# SENSOR.net
KiCad netlist of a schematic drawn in Altium Designer
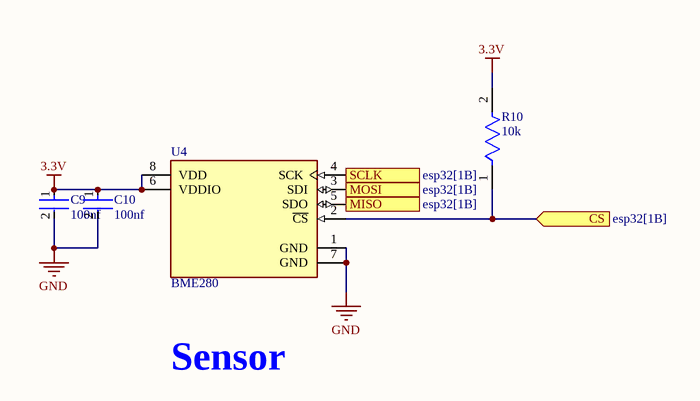
[diagram p0: SENSOR.SchDoc]

(export (version "E")
  (design (tool "Eeschema 10.0.6"))
  (components
    (comp (ref "C9")
      (value "100nf")
      (footprint "FP-CC0603-DA-MFG")
      (description "CAP CER 0.1UF 50V X7R 0603")
      (fields (field (name "MANUFACTURER") "YAGEO") (field (name "VOLTAGE") "50 V"))
      (libsource (lib "Altium Content Vault") (part "11868f565c42a9108669ba33697ecf6"))
    )
    (comp (ref "C10")
      (value "100nf")
      (footprint "FP-CC0603-DA-MFG")
      (description "CAP CER 0.1UF 50V X7R 0603")
      (fields (field (name "MANUFACTURER") "YAGEO") (field (name "VOLTAGE") "50 V"))
      (libsource (lib "Altium Content Vault") (part "11868f565c42a9108669ba33697ecf6"))
    )
    (comp (ref "R10")
      (value "10k")
      (footprint "FP-RC0603-0_55-IPC_C")
      (description "RES 10K OHM 1% 1/10W 0603")
      (fields (field (name "TOLERANCE") "1%"))
      (libsource (lib "Altium Content Vault") (part "1029c3af85768c4190bb7ad29bc67b5"))
    )
    (comp (ref "U4")
      (value "BME280")
      (footprint "FP-BME280-MFG")
      (description "SENSOR PRESSURE HUMIDITY TEMP")
      (libsource (lib "Altium Content Vault") (part "d58e2f6669bc67e6a2bc6a28610ca79"))
    )
  )
  (nets
    (net (code "1") (name "/CS") (class "Default")
      (node (ref "R10") (pin "1") (pinfunction "1_1") (pintype "passive"))
      (node (ref "U4") (pin "2") (pinfunction "~{CS}_2") (pintype "input"))
    )
    (net (code "2") (name "/MISO") (class "Default")
      (node (ref "U4") (pin "5") (pinfunction "SDO_5") (pintype "bidirectional"))
    )
    (net (code "3") (name "/MOSI") (class "Default")
      (node (ref "U4") (pin "3") (pinfunction "SDI_3") (pintype "bidirectional"))
    )
    (net (code "4") (name "/SCLK") (class "Default")
      (node (ref "U4") (pin "4") (pinfunction "SCK_4") (pintype "input"))
    )
    (net (code "5") (name "3.3V") (class "Default")
      (node (ref "C10") (pin "1") (pinfunction "1_1") (pintype "passive"))
      (node (ref "C9") (pin "1") (pinfunction "1_1") (pintype "passive"))
      (node (ref "R10") (pin "2") (pinfunction "2_2") (pintype "passive"))
      (node (ref "U4") (pin "6") (pinfunction "VDDIO_6") (pintype "power_in"))
      (node (ref "U4") (pin "8") (pinfunction "VDD_8") (pintype "power_in"))
    )
    (net (code "6") (name "GND") (class "Default")
      (node (ref "C10") (pin "2") (pinfunction "2_2") (pintype "passive"))
      (node (ref "C9") (pin "2") (pinfunction "2_2") (pintype "passive"))
      (node (ref "U4") (pin "1") (pinfunction "GND_1") (pintype "power_in"))
      (node (ref "U4") (pin "7") (pinfunction "GND_7") (pintype "power_in"))
    )
  )
)
